# Adafruit_INA228_I2C_Power_Monitor.net
KiCad netlist of a schematic drawn in EAGLE
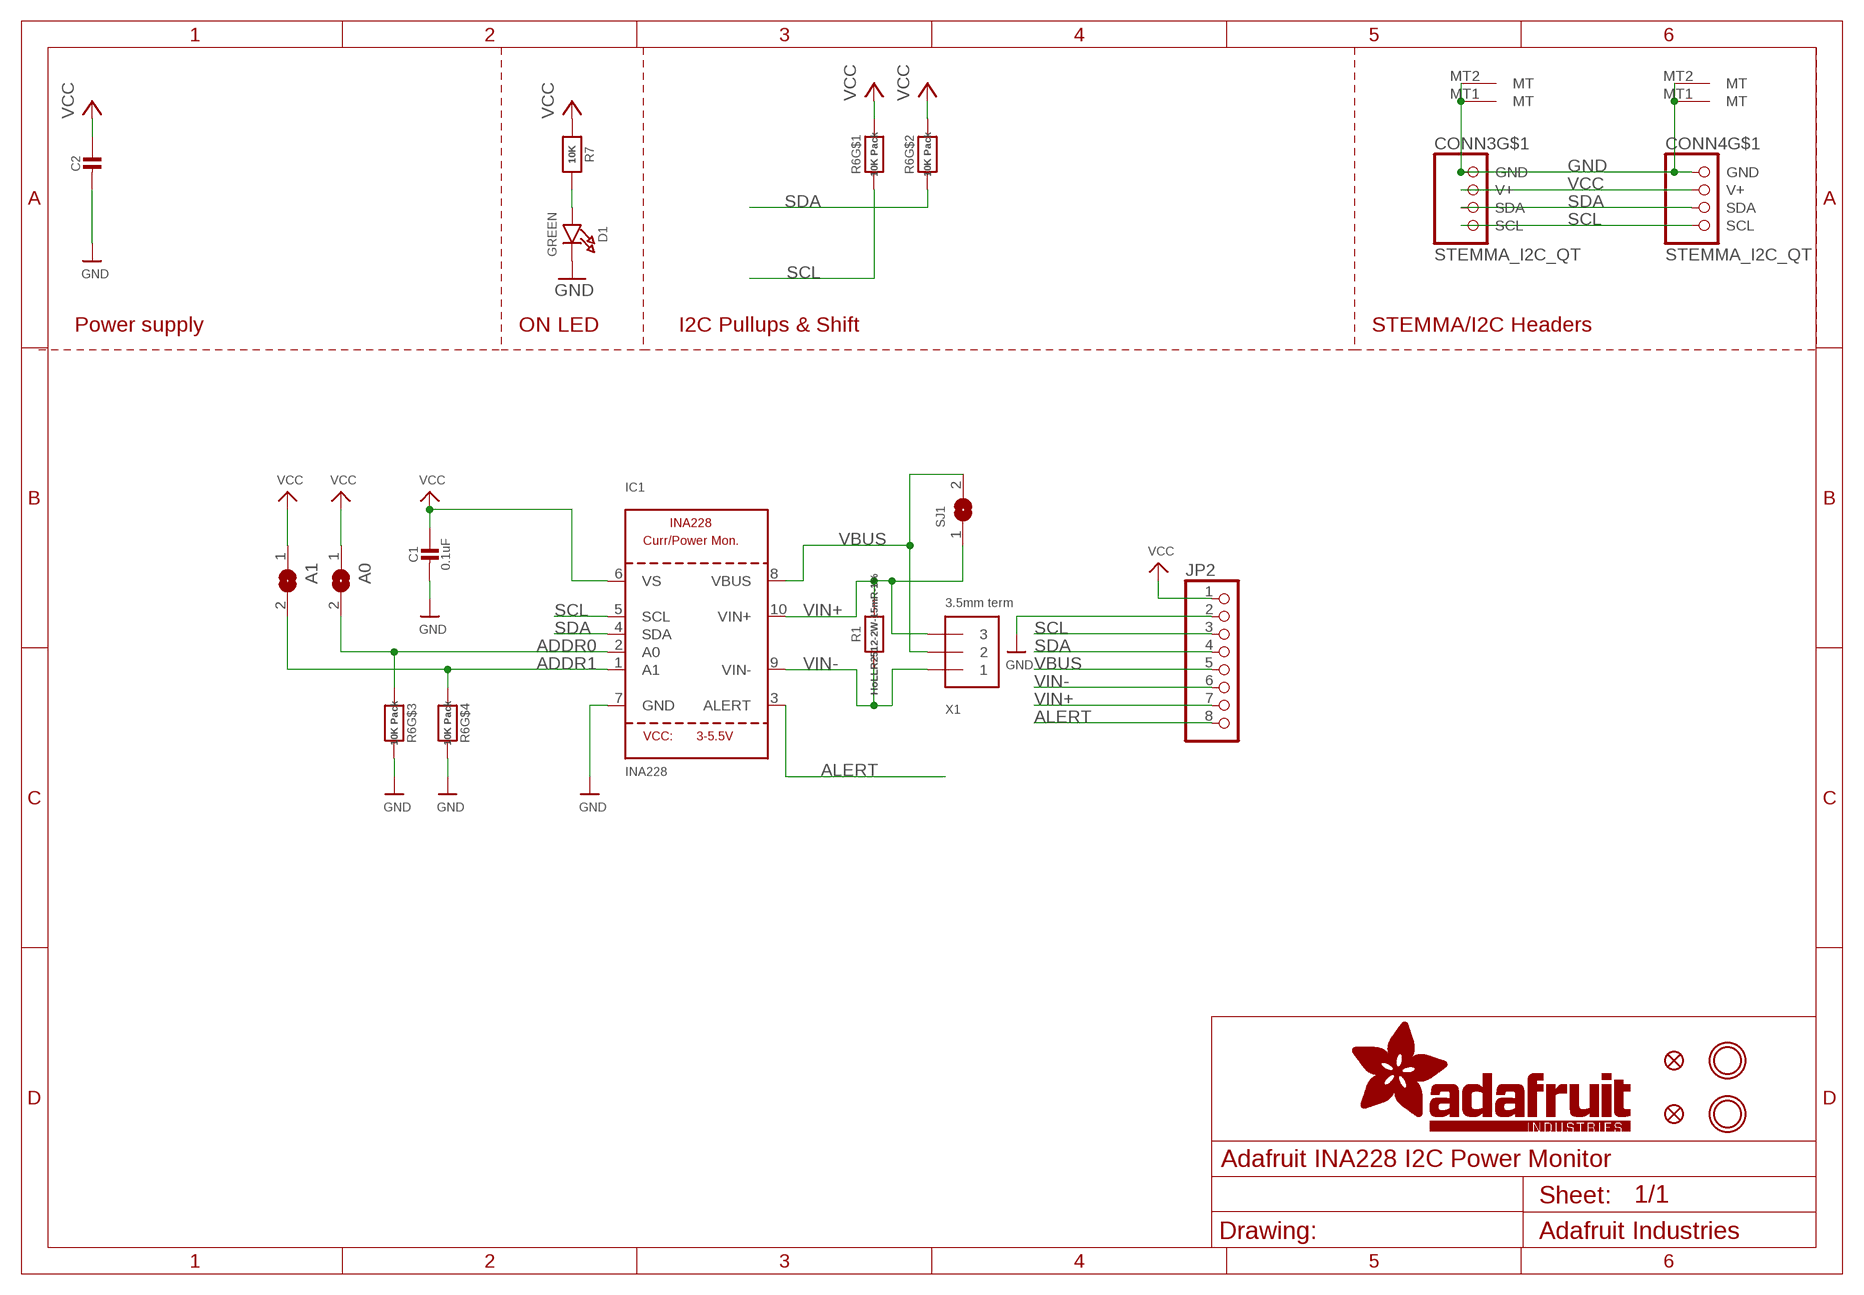
[diagram p0: schematic, sheet 1]

(export (version "E")
  (design (tool "Eeschema 10.0.6"))
  (components
    (comp (ref "A0")
      (value "SOLDERJUMPERREFLOW_NOPASTE")
      (footprint "eagle-import:SOLDERJUMPER_REFLOW_NOPASTE")
      (libsource (lib "eagle-import") (part "SOLDERJUMPERREFLOW_NOPASTE"))
    )
    (comp (ref "A1")
      (value "SOLDERJUMPERREFLOW_NOPASTE")
      (footprint "eagle-import:SOLDERJUMPER_REFLOW_NOPASTE")
      (libsource (lib "eagle-import") (part "SOLDERJUMPERREFLOW_NOPASTE"))
    )
    (comp (ref "C1")
      (value "0.1uF")
      (footprint "eagle-import:0603-NO")
      (libsource (lib "eagle-import") (part "CAP_CERAMIC0603_NO"))
    )
    (comp (ref "C2")
      (value "10uF")
      (footprint "eagle-import:0805-NO")
      (libsource (lib "eagle-import") (part "CAP_CERAMIC0805-NOOUTLINE"))
    )
    (comp (ref "CONN3")
      (value "STEMMA_I2C_QT")
      (footprint "eagle-import:JST_SH4")
      (libsource (lib "eagle-import") (part "STEMMA_I2C_QT"))
    )
    (comp (ref "CONN4")
      (value "STEMMA_I2C_QT")
      (footprint "eagle-import:JST_SH4")
      (libsource (lib "eagle-import") (part "STEMMA_I2C_QT"))
    )
    (comp (ref "D1")
      (value "GREEN")
      (footprint "eagle-import:CHIPLED_0603_NOOUTLINE")
      (libsource (lib "eagle-import") (part "LED0603_NOOUTLINE"))
    )
    (comp (ref "FID3")
      (value "FIDUCIAL_1MM")
      (footprint "eagle-import:FIDUCIAL_1MM")
      (libsource (lib "eagle-import") (part "FIDUCIAL_1MM"))
    )
    (comp (ref "FID4")
      (value "FIDUCIAL_1MM")
      (footprint "eagle-import:FIDUCIAL_1MM")
      (libsource (lib "eagle-import") (part "FIDUCIAL_1MM"))
    )
    (comp (ref "IC1")
      (value "INA228")
      (footprint "eagle-import:MSOP10")
      (libsource (lib "eagle-import") (part "INA228"))
    )
    (comp (ref "JP2")
      (value "HEADER-1X870MIL")
      (footprint "eagle-import:1X08_ROUND_70")
      (libsource (lib "eagle-import") (part "HEADER-1X870MIL"))
    )
    (comp (ref "R1")
      (value "HoLLR2512-2W-15mR-1%")
      (footprint "eagle-import:2512")
      (libsource (lib "eagle-import") (part "RESISTOR2512"))
    )
    (comp (ref "R6")
      (value "10K Pack")
      (footprint "eagle-import:RESPACK_4X0603")
      (libsource (lib "eagle-import") (part "RESISTOR_4PACK"))
    )
    (comp (ref "R7")
      (value "10K")
      (footprint "eagle-import:0603-NO")
      (libsource (lib "eagle-import") (part "RESISTOR_0603_NOOUT"))
    )
    (comp (ref "SJ1")
      (value "SOLDERJUMPER")
      (footprint "eagle-import:SOLDERJUMPER_ARROW_NOPASTE")
      (libsource (lib "eagle-import") (part "SOLDERJUMPER"))
    )
    (comp (ref "U$20")
      (value "MOUNTINGHOLE2.5")
      (footprint "eagle-import:MOUNTINGHOLE_2.5_PLATED")
      (libsource (lib "eagle-import") (part "MOUNTINGHOLE2.5"))
    )
    (comp (ref "U$21")
      (value "MOUNTINGHOLE2.5")
      (footprint "eagle-import:MOUNTINGHOLE_2.5_PLATED")
      (libsource (lib "eagle-import") (part "MOUNTINGHOLE2.5"))
    )
    (comp (ref "X1")
      (value "3.5mm term")
      (footprint "eagle-import:TERMBLOCK_1X3-3.5MM")
      (libsource (lib "eagle-import") (part "TERMBLOCK_1X3"))
    )
  )
  (nets
    (net (code "1") (name "/ADDR0") (class "Default")
      (node (ref "A0") (pin "2") (pinfunction "2_2") (pintype "passive"))
      (node (ref "IC1") (pin "2") (pinfunction "A0_2") (pintype "input"))
      (node (ref "R6") (pin "3") (pinfunction "1_3") (pintype "passive"))
    )
    (net (code "2") (name "/ADDR1") (class "Default")
      (node (ref "A1") (pin "2") (pinfunction "2_2") (pintype "passive"))
      (node (ref "IC1") (pin "1") (pinfunction "A1_1") (pintype "input"))
      (node (ref "R6") (pin "4") (pinfunction "1_4") (pintype "passive"))
    )
    (net (code "3") (name "/ALERT") (class "Default")
      (node (ref "IC1") (pin "3") (pinfunction "ALERT_3") (pintype "output"))
      (node (ref "JP2") (pin "8") (pinfunction "8_8") (pintype "passive"))
    )
    (net (code "4") (name "/SCL") (class "Default")
      (node (ref "CONN3") (pin "4") (pinfunction "SCL_4") (pintype "passive"))
      (node (ref "CONN4") (pin "4") (pinfunction "SCL_4") (pintype "passive"))
      (node (ref "IC1") (pin "5") (pinfunction "SCL_5") (pintype "bidirectional"))
      (node (ref "JP2") (pin "3") (pinfunction "3_3") (pintype "passive"))
      (node (ref "R6") (pin "1") (pinfunction "1_1") (pintype "passive"))
    )
    (net (code "5") (name "/SDA") (class "Default")
      (node (ref "CONN3") (pin "3") (pinfunction "SDA_3") (pintype "passive"))
      (node (ref "CONN4") (pin "3") (pinfunction "SDA_3") (pintype "passive"))
      (node (ref "IC1") (pin "4") (pinfunction "SDA_4") (pintype "bidirectional"))
      (node (ref "JP2") (pin "4") (pinfunction "4_4") (pintype "passive"))
      (node (ref "R6") (pin "2") (pinfunction "1_2") (pintype "passive"))
    )
    (net (code "6") (name "/VBUS") (class "Default")
      (node (ref "IC1") (pin "8") (pinfunction "VBUS_8") (pintype "power_in"))
      (node (ref "JP2") (pin "5") (pinfunction "5_5") (pintype "passive"))
      (node (ref "SJ1") (pin "2") (pinfunction "2_2") (pintype "passive"))
      (node (ref "X1") (pin "2") (pinfunction "2_2") (pintype "passive"))
    )
    (net (code "7") (name "/VIN+") (class "Default")
      (node (ref "IC1") (pin "10") (pinfunction "VIN+_10") (pintype "bidirectional"))
      (node (ref "JP2") (pin "7") (pinfunction "7_7") (pintype "passive"))
      (node (ref "R1") (pin "2") (pinfunction "2_2") (pintype "passive"))
      (node (ref "SJ1") (pin "1") (pinfunction "1_1") (pintype "passive"))
      (node (ref "X1") (pin "3") (pinfunction "3_3") (pintype "passive"))
    )
    (net (code "8") (name "/VIN-") (class "Default")
      (node (ref "IC1") (pin "9") (pinfunction "VIN-_9") (pintype "bidirectional"))
      (node (ref "JP2") (pin "6") (pinfunction "6_6") (pintype "passive"))
      (node (ref "R1") (pin "1") (pinfunction "1_1") (pintype "passive"))
      (node (ref "X1") (pin "1") (pinfunction "1_1") (pintype "passive"))
    )
    (net (code "9") (name "GND") (class "Default")
      (node (ref "C1") (pin "2") (pinfunction "2_2") (pintype "passive"))
      (node (ref "C2") (pin "2") (pinfunction "2_2") (pintype "passive"))
      (node (ref "CONN3") (pin "1") (pinfunction "GND_1") (pintype "passive"))
      (node (ref "CONN3") (pin "MT1") (pinfunction "MT_MT1") (pintype "bidirectional"))
      (node (ref "CONN3") (pin "MT2") (pinfunction "MT_MT2") (pintype "bidirectional"))
      (node (ref "CONN4") (pin "1") (pinfunction "GND_1") (pintype "passive"))
      (node (ref "CONN4") (pin "MT1") (pinfunction "MT_MT1") (pintype "bidirectional"))
      (node (ref "CONN4") (pin "MT2") (pinfunction "MT_MT2") (pintype "bidirectional"))
      (node (ref "D1") (pin "C") (pinfunction "C_C") (pintype "passive"))
      (node (ref "IC1") (pin "7") (pinfunction "GND_7") (pintype "power_in"))
      (node (ref "JP2") (pin "2") (pinfunction "2_2") (pintype "passive"))
      (node (ref "R6") (pin "5") (pinfunction "2_5") (pintype "passive"))
      (node (ref "R6") (pin "6") (pinfunction "2_6") (pintype "passive"))
    )
    (net (code "10") (name "Net-(D1-PadA)") (class "Default")
      (node (ref "D1") (pin "A") (pinfunction "A_A") (pintype "passive"))
      (node (ref "R7") (pin "2") (pinfunction "2_2") (pintype "passive"))
    )
    (net (code "11") (name "VCC") (class "Default")
      (node (ref "A0") (pin "1") (pinfunction "1_1") (pintype "passive"))
      (node (ref "A1") (pin "1") (pinfunction "1_1") (pintype "passive"))
      (node (ref "C1") (pin "1") (pinfunction "1_1") (pintype "passive"))
      (node (ref "C2") (pin "1") (pinfunction "1_1") (pintype "passive"))
      (node (ref "CONN3") (pin "2") (pinfunction "V+_2") (pintype "passive"))
      (node (ref "CONN4") (pin "2") (pinfunction "V+_2") (pintype "passive"))
      (node (ref "IC1") (pin "6") (pinfunction "VS_6") (pintype "power_in"))
      (node (ref "JP2") (pin "1") (pinfunction "1_1") (pintype "passive"))
      (node (ref "R6") (pin "7") (pinfunction "2_7") (pintype "passive"))
      (node (ref "R6") (pin "8") (pinfunction "2_8") (pintype "passive"))
      (node (ref "R7") (pin "1") (pinfunction "1_1") (pintype "passive"))
    )
  )
)
